# Serial-Basic.net
KiCad netlist of a schematic drawn in EAGLE
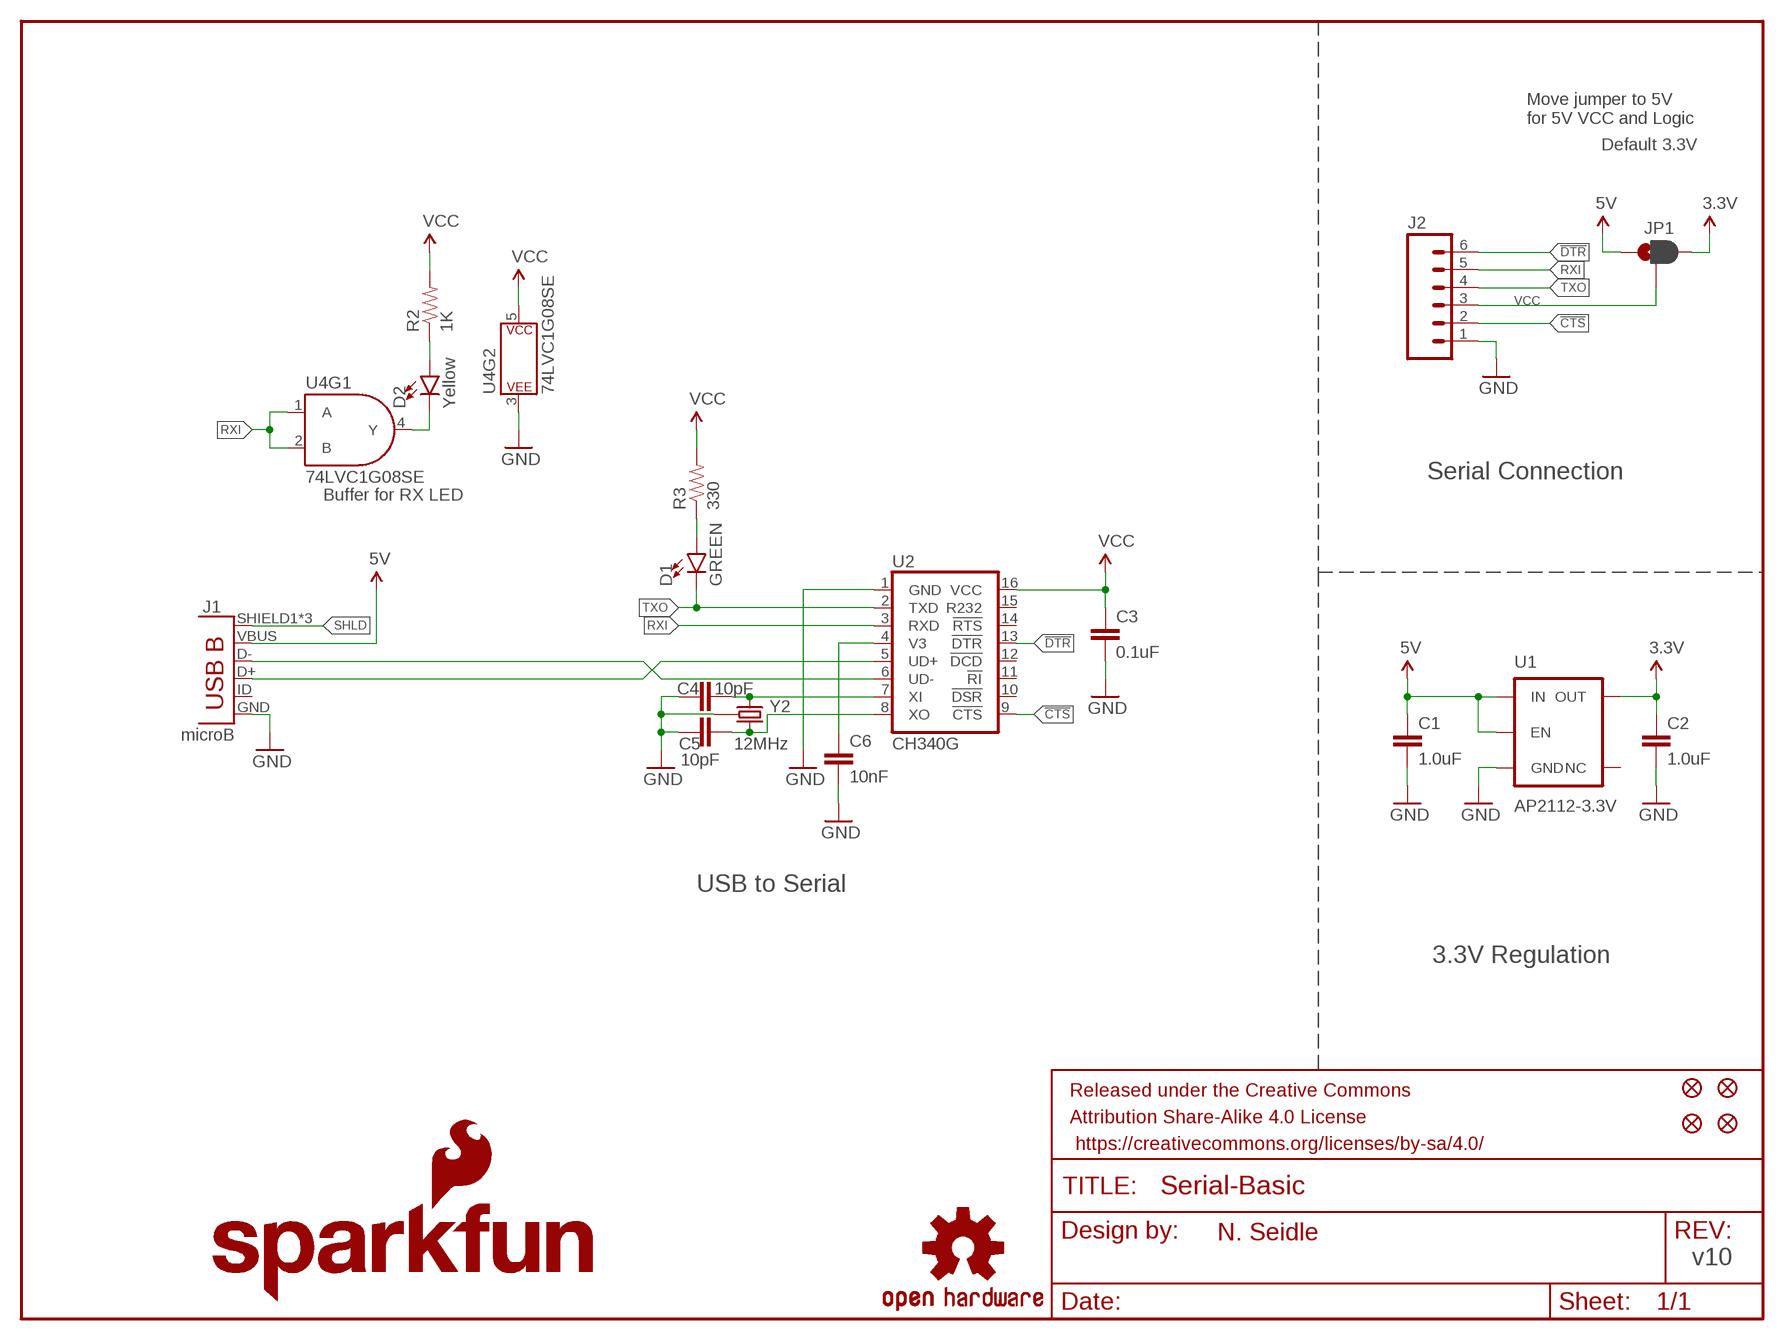
[diagram p0: schematic, sheet 1]

(export (version "E")
  (design (tool "Eeschema 10.0.6"))
  (components
    (comp (ref "C1")
      (value "1.0uF")
      (footprint "eagle-import:0603-CAP")
      (libsource (lib "eagle-import") (part "1.0UF-16V-10%(0603)"))
    )
    (comp (ref "C2")
      (value "1.0uF")
      (footprint "eagle-import:0603-CAP")
      (libsource (lib "eagle-import") (part "1.0UF-16V-10%(0603)"))
    )
    (comp (ref "C3")
      (value "0.1uF")
      (footprint "eagle-import:0603-CAP")
      (libsource (lib "eagle-import") (part "0.1UF-25V(+80/-20%)(0603)"))
    )
    (comp (ref "C4")
      (value "10pF")
      (footprint "eagle-import:0603-CAP")
      (libsource (lib "eagle-import") (part "10PF-50V-5%(0603)"))
    )
    (comp (ref "C5")
      (value "10pF")
      (footprint "eagle-import:0603-CAP")
      (libsource (lib "eagle-import") (part "10PF-50V-5%(0603)"))
    )
    (comp (ref "C6")
      (value "10nF")
      (footprint "eagle-import:0603-CAP")
      (libsource (lib "eagle-import") (part "10NF/10000PF-50V-10%(0603)"))
    )
    (comp (ref "D1")
      (value "GREEN")
      (footprint "eagle-import:LED-0603")
      (libsource (lib "eagle-import") (part "LED-GREEN0603"))
    )
    (comp (ref "D2")
      (value "Yellow")
      (footprint "eagle-import:LED-0603")
      (libsource (lib "eagle-import") (part "LED-YELLOW0603"))
    )
    (comp (ref "FRAME1")
      (value "FRAME-LETTER")
      (footprint "eagle-import:CREATIVE_COMMONS")
      (libsource (lib "eagle-import") (part "FRAME-LETTER"))
    )
    (comp (ref "J1")
      (value "microB")
      (footprint "eagle-import:USB-B-MICRO-SMD_V03")
      (libsource (lib "eagle-import") (part "USB-MICROB{dblquote}"))
    )
    (comp (ref "J2")
      (value "M06SMD-FEMALE-V2")
      (footprint "eagle-import:1X06-SMD-FEMALE-V2")
      (libsource (lib "eagle-import") (part "M06SMD-FEMALE-V2"))
    )
    (comp (ref "JP1")
      (value "JUMPER-PAD-3-2OF3_NC_BY_PASTE")
      (footprint "eagle-import:PAD-JUMPER-3-2OF3_NC_BY_PASTE_YES_SILK_FULL_BOX")
      (libsource (lib "eagle-import") (part "JUMPER-PAD-3-2OF3_NC_BY_PASTE"))
    )
    (comp (ref "JP3")
      (value "FIDUCIAL1X2")
      (footprint "eagle-import:FIDUCIAL-1X2")
      (libsource (lib "eagle-import") (part "FIDUCIAL1X2"))
    )
    (comp (ref "JP4")
      (value "FIDUCIAL1X2")
      (footprint "eagle-import:FIDUCIAL-1X2")
      (libsource (lib "eagle-import") (part "FIDUCIAL1X2"))
    )
    (comp (ref "JP5")
      (value "FIDUCIAL1X2")
      (footprint "eagle-import:FIDUCIAL-1X2")
      (libsource (lib "eagle-import") (part "FIDUCIAL1X2"))
    )
    (comp (ref "JP6")
      (value "FIDUCIAL1X2")
      (footprint "eagle-import:FIDUCIAL-1X2")
      (libsource (lib "eagle-import") (part "FIDUCIAL1X2"))
    )
    (comp (ref "LOGO1")
      (value "OSHW-LOGOS")
      (footprint "eagle-import:OSHW-LOGO-S")
      (libsource (lib "eagle-import") (part "OSHW-LOGOS"))
    )
    (comp (ref "LOGO2")
      (value "SFE_LOGO_FLAME.1_INCH")
      (footprint "eagle-import:SFE_LOGO_FLAME_.1")
      (libsource (lib "eagle-import") (part "SFE_LOGO_FLAME.1_INCH"))
    )
    (comp (ref "LOGO3")
      (value "SFE_LOGO_NAME.1_INCH")
      (footprint "eagle-import:SFE_LOGO_NAME_.1")
      (libsource (lib "eagle-import") (part "SFE_LOGO_NAME.1_INCH"))
    )
    (comp (ref "R2")
      (value "1K")
      (footprint "eagle-import:0603-RES")
      (libsource (lib "eagle-import") (part "1KOHM-1/10W-1%(0603)"))
    )
    (comp (ref "R3")
      (value "330")
      (footprint "eagle-import:0603-RES")
      (libsource (lib "eagle-import") (part "330OHM1/10W1%(0603)"))
    )
    (comp (ref "U1")
      (value "AP2112-3.3V")
      (footprint "eagle-import:SOT23-5")
      (libsource (lib "eagle-import") (part "V_REG_AP2112K-3.3V"))
    )
    (comp (ref "U2")
      (value "CH340G")
      (footprint "eagle-import:SO016")
      (libsource (lib "eagle-import") (part "CH340GSMD"))
    )
    (comp (ref "U4")
      (value "74LVC1G08SE")
      (footprint "eagle-import:SOT353")
      (libsource (lib "eagle-import") (part "7408"))
    )
    (comp (ref "Y2")
      (value "12MHz")
      (footprint "eagle-import:CRYSTAL-SMD-3.2X2.5")
      (libsource (lib "eagle-import") (part "CRYSTAL-GROUNDED3.2X2.5"))
    )
  )
  (nets
    (net (code "1") (name "/~{CTS}") (class "Default")
      (node (ref "J2") (pin "2") (pinfunction "2_2") (pintype "passive"))
      (node (ref "U2") (pin "9") (pinfunction "~{CTS}_9") (pintype "bidirectional"))
    )
    (net (code "2") (name "/~{DTR}") (class "Default")
      (node (ref "J2") (pin "6") (pinfunction "6_6") (pintype "passive"))
      (node (ref "U2") (pin "13") (pinfunction "~{DTR}_13") (pintype "bidirectional"))
    )
    (net (code "3") (name "3.3V") (class "Default")
      (node (ref "C2") (pin "1") (pinfunction "1_1") (pintype "passive"))
      (node (ref "JP1") (pin "3") (pinfunction "3_3") (pintype "passive"))
      (node (ref "U1") (pin "5") (pinfunction "OUT_5") (pintype "passive"))
    )
    (net (code "4") (name "5V") (class "Default")
      (node (ref "C1") (pin "1") (pinfunction "1_1") (pintype "passive"))
      (node (ref "J1") (pin "VBUS") (pinfunction "VBUS_VBUS") (pintype "bidirectional"))
      (node (ref "JP1") (pin "1") (pinfunction "1_1") (pintype "passive"))
      (node (ref "U1") (pin "1") (pinfunction "IN_1") (pintype "input"))
      (node (ref "U1") (pin "3") (pinfunction "EN_3") (pintype "input"))
    )
    (net (code "5") (name "GND") (class "Default")
      (node (ref "C1") (pin "2") (pinfunction "2_2") (pintype "passive"))
      (node (ref "C2") (pin "2") (pinfunction "2_2") (pintype "passive"))
      (node (ref "C3") (pin "2") (pinfunction "2_2") (pintype "passive"))
      (node (ref "C4") (pin "1") (pinfunction "1_1") (pintype "passive"))
      (node (ref "C5") (pin "1") (pinfunction "1_1") (pintype "passive"))
      (node (ref "C6") (pin "2") (pinfunction "2_2") (pintype "passive"))
      (node (ref "J1") (pin "GND") (pinfunction "GND_GND") (pintype "bidirectional"))
      (node (ref "J2") (pin "1") (pinfunction "1_1") (pintype "passive"))
      (node (ref "U1") (pin "2") (pinfunction "GND_2") (pintype "input"))
      (node (ref "U2") (pin "1") (pinfunction "GND_1") (pintype "bidirectional"))
      (node (ref "U4") (pin "3") (pinfunction "P$V-_3") (pintype "bidirectional"))
      (node (ref "Y2") (pin "2") (pinfunction "GND_2") (pintype "passive"))
      (node (ref "Y2") (pin "4") (pinfunction "GND_4") (pintype "passive"))
    )
    (net (code "6") (name "Net-(D1-PadA)") (class "Default")
      (node (ref "D1") (pin "A") (pinfunction "A_A") (pintype "passive"))
      (node (ref "R3") (pin "1") (pinfunction "1_1") (pintype "passive"))
    )
    (net (code "7") (name "Net-(D2-PadA)") (class "Default")
      (node (ref "D2") (pin "A") (pinfunction "A_A") (pintype "passive"))
      (node (ref "R2") (pin "1") (pinfunction "1_1") (pintype "passive"))
    )
    (net (code "8") (name "Net-(U2-UD+)") (class "Default")
      (node (ref "J1") (pin "D+") (pinfunction "D+_D+") (pintype "bidirectional"))
      (node (ref "U2") (pin "5") (pinfunction "UD+_5") (pintype "bidirectional"))
    )
    (net (code "9") (name "Net-(U2-UD-)") (class "Default")
      (node (ref "J1") (pin "D-") (pinfunction "D-_D-") (pintype "bidirectional"))
      (node (ref "U2") (pin "6") (pinfunction "UD-_6") (pintype "bidirectional"))
    )
    (net (code "10") (name "Net-(U2-V3)") (class "Default")
      (node (ref "C6") (pin "1") (pinfunction "1_1") (pintype "passive"))
      (node (ref "U2") (pin "4") (pinfunction "V3_4") (pintype "bidirectional"))
    )
    (net (code "11") (name "Net-(U2-XI)") (class "Default")
      (node (ref "C4") (pin "2") (pinfunction "2_2") (pintype "passive"))
      (node (ref "U2") (pin "7") (pinfunction "XI_7") (pintype "bidirectional"))
      (node (ref "Y2") (pin "1") (pinfunction "1_1") (pintype "passive"))
    )
    (net (code "12") (name "Net-(U2-XO)") (class "Default")
      (node (ref "C5") (pin "2") (pinfunction "2_2") (pintype "passive"))
      (node (ref "U2") (pin "8") (pinfunction "XO_8") (pintype "bidirectional"))
      (node (ref "Y2") (pin "3") (pinfunction "2_3") (pintype "passive"))
    )
    (net (code "13") (name "Net-(U4A-Y)") (class "Default")
      (node (ref "D2") (pin "C") (pinfunction "C_C") (pintype "passive"))
      (node (ref "U4") (pin "4") (pinfunction "Y_4") (pintype "bidirectional"))
    )
    (net (code "14") (name "RXI") (class "Default")
      (node (ref "J2") (pin "5") (pinfunction "5_5") (pintype "passive"))
      (node (ref "U2") (pin "3") (pinfunction "RXD_3") (pintype "bidirectional"))
      (node (ref "U4") (pin "1") (pinfunction "A_1") (pintype "bidirectional"))
      (node (ref "U4") (pin "2") (pinfunction "B_2") (pintype "bidirectional"))
    )
    (net (code "15") (name "SHLD") (class "Default")
      (node (ref "J1") (pin "SHIELD1") (pinfunction "SHIELD_SHIELD1") (pintype "bidirectional"))
      (node (ref "J1") (pin "SHIELD2") (pinfunction "SHIELD_SHIELD2") (pintype "bidirectional"))
      (node (ref "J1") (pin "SHIELD3") (pinfunction "SHIELD_SHIELD3") (pintype "bidirectional"))
    )
    (net (code "16") (name "TXO") (class "Default")
      (node (ref "D1") (pin "C") (pinfunction "C_C") (pintype "passive"))
      (node (ref "J2") (pin "4") (pinfunction "4_4") (pintype "passive"))
      (node (ref "U2") (pin "2") (pinfunction "TXD_2") (pintype "bidirectional"))
    )
    (net (code "17") (name "VCC") (class "Default")
      (node (ref "C3") (pin "1") (pinfunction "1_1") (pintype "passive"))
      (node (ref "J2") (pin "3") (pinfunction "3_3") (pintype "passive"))
      (node (ref "JP1") (pin "2") (pinfunction "2_2") (pintype "passive"))
      (node (ref "R2") (pin "2") (pinfunction "2_2") (pintype "passive"))
      (node (ref "R3") (pin "2") (pinfunction "2_2") (pintype "passive"))
      (node (ref "U2") (pin "16") (pinfunction "VCC_16") (pintype "bidirectional"))
      (node (ref "U4") (pin "5") (pinfunction "P$V+_5") (pintype "bidirectional"))
    )
    (net (code "18") (name "unconnected-(J1-USBID-PadID)") (class "Default")
      (node (ref "J1") (pin "ID") (pinfunction "USBID_ID") (pintype "bidirectional"))
    )
    (net (code "19") (name "unconnected-(U1-NC-Pad4)") (class "Default")
      (node (ref "U1") (pin "4") (pinfunction "NC_4") (pintype "input"))
    )
    (net (code "20") (name "unconnected-(U2-R232-Pad15)") (class "Default")
      (node (ref "U2") (pin "15") (pinfunction "R232_15") (pintype "bidirectional"))
    )
    (net (code "21") (name "unconnected-(U2-~{DCD}-Pad12)") (class "Default")
      (node (ref "U2") (pin "12") (pinfunction "~{DCD}_12") (pintype "bidirectional"))
    )
    (net (code "22") (name "unconnected-(U2-~{DSR}-Pad10)") (class "Default")
      (node (ref "U2") (pin "10") (pinfunction "~{DSR}_10") (pintype "bidirectional"))
    )
    (net (code "23") (name "unconnected-(U2-~{RI}-Pad11)") (class "Default")
      (node (ref "U2") (pin "11") (pinfunction "~{RI}_11") (pintype "bidirectional"))
    )
    (net (code "24") (name "unconnected-(U2-~{RTS}-Pad14)") (class "Default")
      (node (ref "U2") (pin "14") (pinfunction "~{RTS}_14") (pintype "bidirectional"))
    )
  )
)
